# schematic.net
KiCad netlist of a schematic drawn in EAGLE
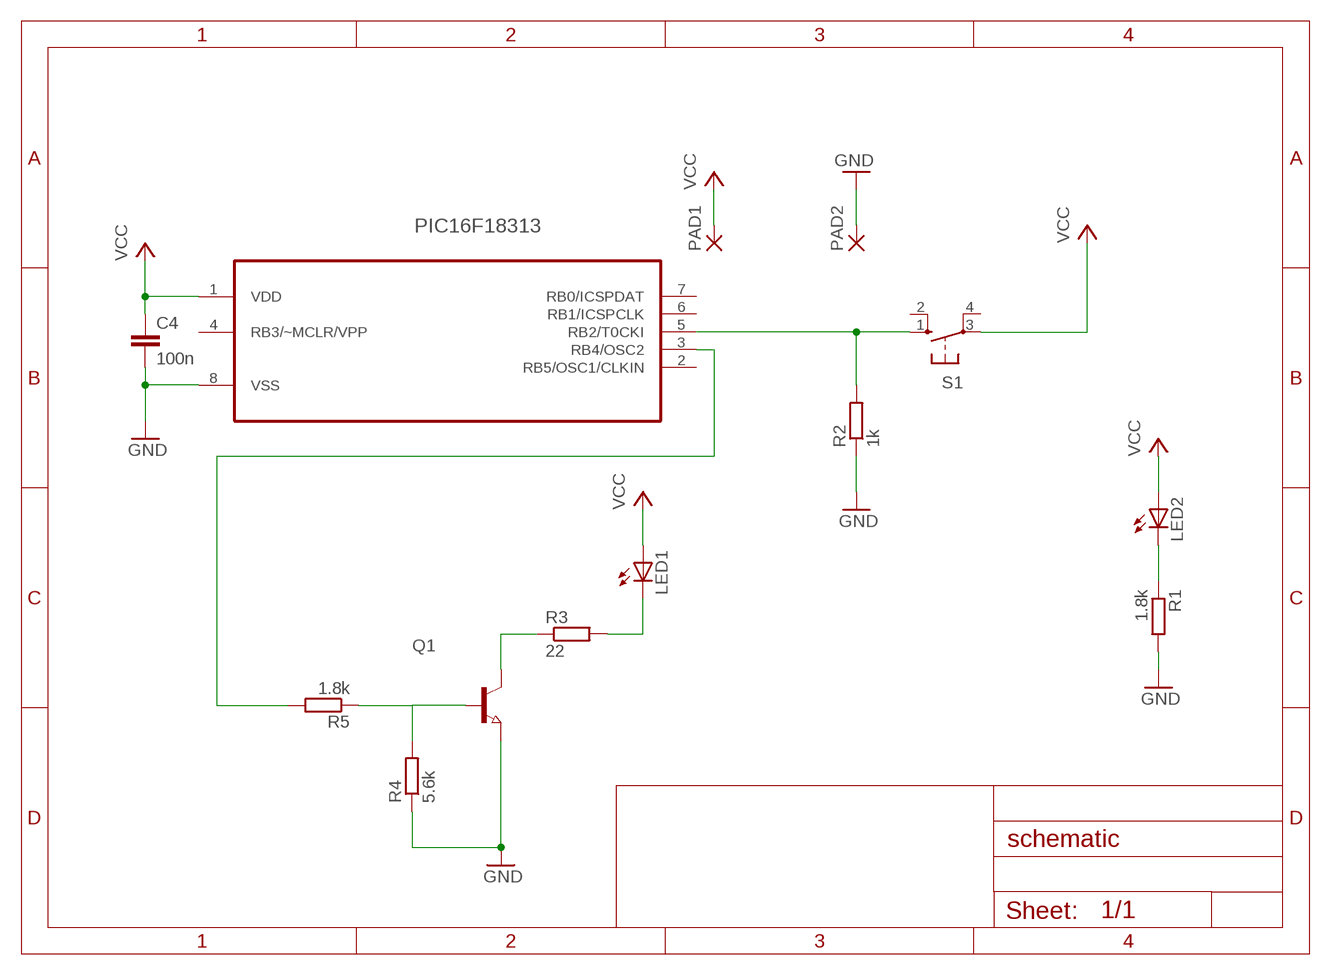
[diagram p0: schematic, sheet 1]

(export (version "E")
  (design (tool "Eeschema 10.0.6"))
  (components
    (comp (ref "C4")
      (value "100n")
      (footprint "eagle-import:C1206")
      (libsource (lib "eagle-import") (part "C-EUC1206"))
    )
    (comp (ref "LED1")
      (value "LED3MM")
      (footprint "eagle-import:LED3MM")
      (libsource (lib "eagle-import") (part "LED3MM"))
    )
    (comp (ref "LED2")
      (value "LEDCHIPLED_1206")
      (footprint "eagle-import:CHIPLED_1206")
      (libsource (lib "eagle-import") (part "LEDCHIPLED_1206"))
    )
    (comp (ref "PAD1")
      (value "2,54/0,9")
      (footprint "eagle-import:2,54_0,9")
      (libsource (lib "eagle-import") (part "2,54/0,9"))
    )
    (comp (ref "PAD2")
      (value "2,54/0,9")
      (footprint "eagle-import:2,54_0,9")
      (libsource (lib "eagle-import") (part "2,54/0,9"))
    )
    (comp (ref "PIC16F18313")
      (value "PIC12F519-I/P")
      (footprint "eagle-import:DIP254P762X533-8")
      (fields (field (name "MPN") "PIC18F18313-I/P"))
      (libsource (lib "eagle-import") (part "PIC12F519-I/P"))
    )
    (comp (ref "Q1")
      (value "NPN-TRANSISTOR_SOT23")
      (footprint "eagle-import:SOT23")
      (libsource (lib "eagle-import") (part "NPN-TRANSISTOR_SOT23"))
    )
    (comp (ref "R1")
      (value "1.8k")
      (footprint "eagle-import:M1206")
      (libsource (lib "eagle-import") (part "R-EU_M1206"))
    )
    (comp (ref "R2")
      (value "1k")
      (footprint "eagle-import:M1206")
      (libsource (lib "eagle-import") (part "R-EU_M1206"))
    )
    (comp (ref "R3")
      (value "22")
      (footprint "eagle-import:M1206")
      (libsource (lib "eagle-import") (part "R-EU_M1206"))
    )
    (comp (ref "R4")
      (value "5.6k")
      (footprint "eagle-import:M1206")
      (libsource (lib "eagle-import") (part "R-EU_M1206"))
    )
    (comp (ref "R5")
      (value "1.8k")
      (footprint "eagle-import:M1206")
      (libsource (lib "eagle-import") (part "R-EU_M1206"))
    )
    (comp (ref "S1")
      (value "10-XX")
      (footprint "eagle-import:B3F-10XX")
      (fields (field (name "MPN") "B3F-1000"))
      (libsource (lib "eagle-import") (part "10-XX"))
    )
  )
  (nets
    (net (code "1") (name "GND") (class "Default")
      (node (ref "C4") (pin "2") (pinfunction "2_2") (pintype "passive"))
      (node (ref "PAD2") (pin "1") (pinfunction "P_1") (pintype "passive"))
      (node (ref "PIC16F18313") (pin "8") (pinfunction "VSS_8") (pintype "passive"))
      (node (ref "Q1") (pin "2") (pinfunction "E_2") (pintype "passive"))
      (node (ref "R1") (pin "2") (pinfunction "2_2") (pintype "passive"))
      (node (ref "R2") (pin "1") (pinfunction "1_1") (pintype "passive"))
      (node (ref "R4") (pin "1") (pinfunction "1_1") (pintype "passive"))
    )
    (net (code "2") (name "Net-(LED1-C)") (class "Default")
      (node (ref "LED1") (pin "K") (pinfunction "C_K") (pintype "passive"))
      (node (ref "R3") (pin "2") (pinfunction "2_2") (pintype "passive"))
    )
    (net (code "3") (name "Net-(LED2-PadC)") (class "Default")
      (node (ref "LED2") (pin "C") (pinfunction "C_C") (pintype "passive"))
      (node (ref "R1") (pin "1") (pinfunction "1_1") (pintype "passive"))
    )
    (net (code "4") (name "Net-(PIC16F18313-RB2{slash}T0CKI)") (class "Default")
      (node (ref "PIC16F18313") (pin "5") (pinfunction "RB2/T0CKI_5") (pintype "bidirectional"))
      (node (ref "R2") (pin "2") (pinfunction "2_2") (pintype "passive"))
      (node (ref "S1") (pin "1") (pinfunction "S_1") (pintype "passive"))
    )
    (net (code "5") (name "Net-(PIC16F18313-RB4{slash}OSC2)") (class "Default")
      (node (ref "PIC16F18313") (pin "3") (pinfunction "RB4/OSC2_3") (pintype "bidirectional"))
      (node (ref "R5") (pin "2") (pinfunction "2_2") (pintype "passive"))
    )
    (net (code "6") (name "Net-(Q1-B)") (class "Default")
      (node (ref "Q1") (pin "1") (pinfunction "B_1") (pintype "passive"))
      (node (ref "R4") (pin "2") (pinfunction "2_2") (pintype "passive"))
      (node (ref "R5") (pin "1") (pinfunction "1_1") (pintype "passive"))
    )
    (net (code "7") (name "Net-(Q1-C)") (class "Default")
      (node (ref "Q1") (pin "3") (pinfunction "C_3") (pintype "passive"))
      (node (ref "R3") (pin "1") (pinfunction "1_1") (pintype "passive"))
    )
    (net (code "8") (name "VCC") (class "Default")
      (node (ref "C4") (pin "1") (pinfunction "1_1") (pintype "passive"))
      (node (ref "LED1") (pin "A") (pinfunction "A_A") (pintype "passive"))
      (node (ref "LED2") (pin "A") (pinfunction "A_A") (pintype "passive"))
      (node (ref "PAD1") (pin "1") (pinfunction "P_1") (pintype "passive"))
      (node (ref "PIC16F18313") (pin "1") (pinfunction "VDD_1") (pintype "power_in"))
      (node (ref "S1") (pin "3") (pinfunction "P_3") (pintype "passive"))
    )
    (net (code "9") (name "unconnected-(PIC16F18313-RB0{slash}ICSPDAT-Pad7)") (class "Default")
      (node (ref "PIC16F18313") (pin "7") (pinfunction "RB0/ICSPDAT_7") (pintype "bidirectional"))
    )
    (net (code "10") (name "unconnected-(PIC16F18313-RB1{slash}ICSPCLK-Pad6)") (class "Default")
      (node (ref "PIC16F18313") (pin "6") (pinfunction "RB1/ICSPCLK_6") (pintype "bidirectional"))
    )
    (net (code "11") (name "unconnected-(PIC16F18313-RB3{slash}~{MCLR{slash}VPP}-Pad4)") (class "Default")
      (node (ref "PIC16F18313") (pin "4") (pinfunction "RB3/~{MCLR/VPP}_4") (pintype "input"))
    )
    (net (code "12") (name "unconnected-(PIC16F18313-RB5{slash}OSC1{slash}CLKIN-Pad2)") (class "Default")
      (node (ref "PIC16F18313") (pin "2") (pinfunction "RB5/OSC1/CLKIN_2") (pintype "bidirectional"))
    )
    (net (code "13") (name "unconnected-(S1-P1-Pad4)") (class "Default")
      (node (ref "S1") (pin "4") (pinfunction "P1_4") (pintype "passive"))
    )
    (net (code "14") (name "unconnected-(S1-S1-Pad2)") (class "Default")
      (node (ref "S1") (pin "2") (pinfunction "S1_2") (pintype "passive"))
    )
  )
)
